# SmartBuoyLoRa.net
KiCad netlist of a schematic drawn in Altium Designer
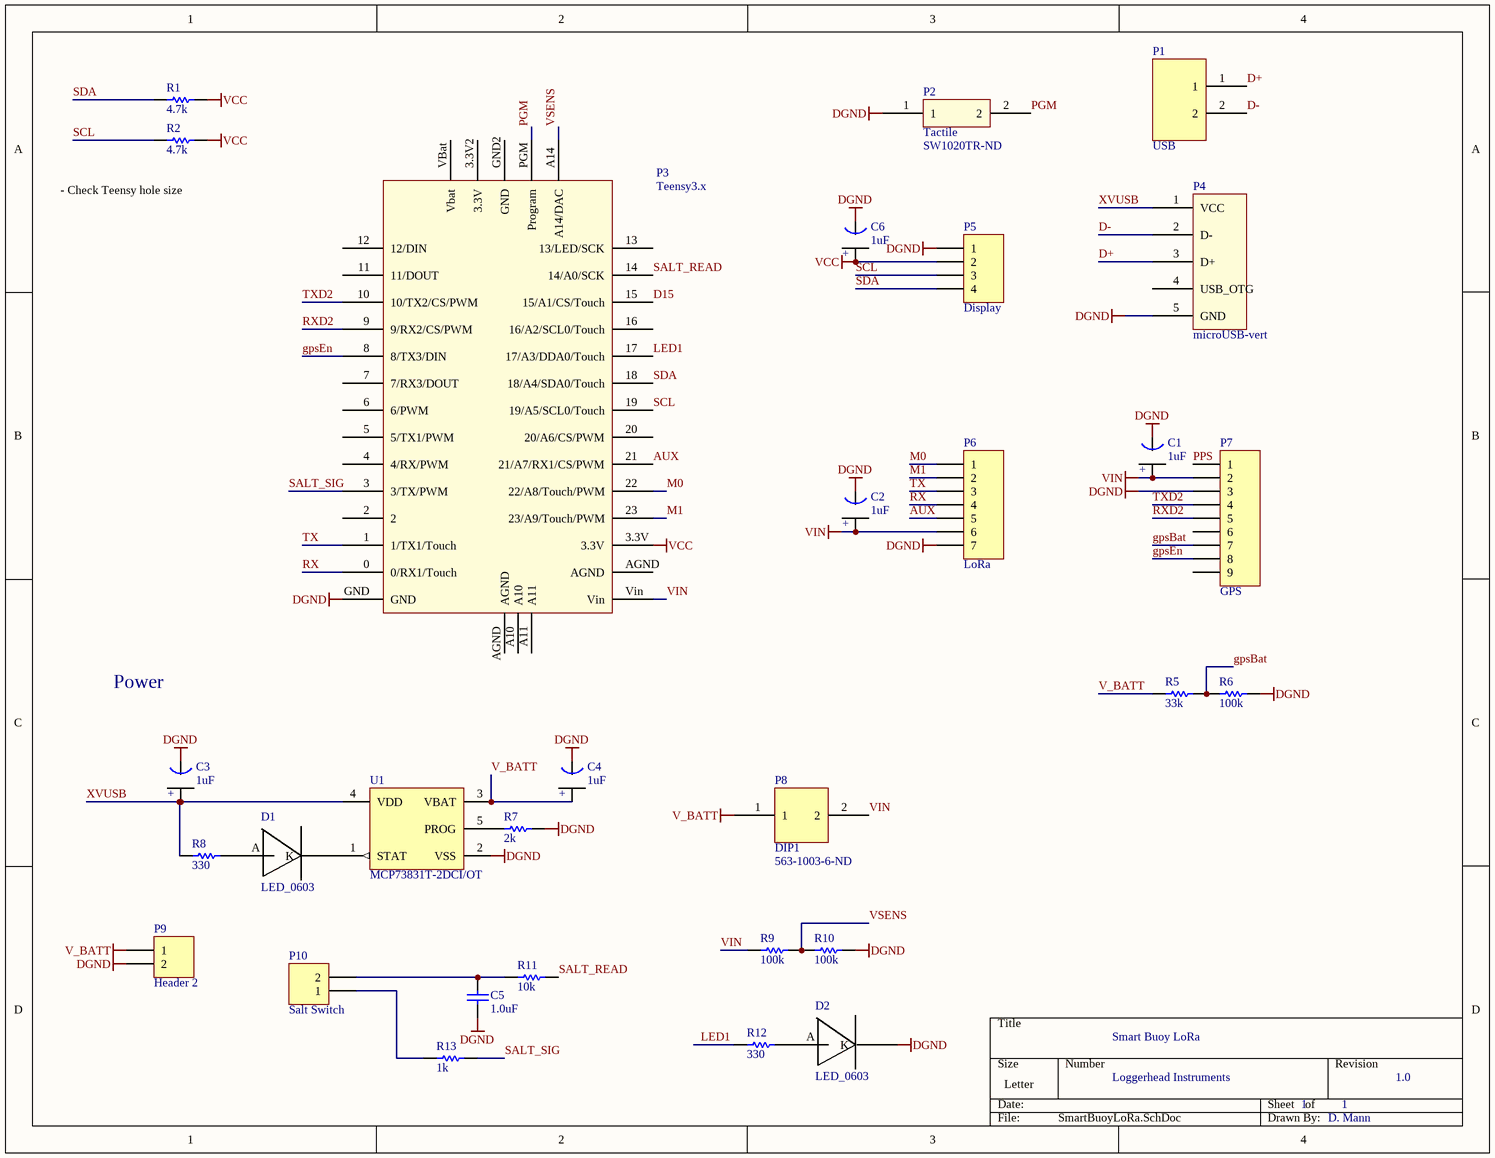
[diagram p0: SmartBuoyLoRa.SchDoc]

(export (version "E")
  (design (tool "Eeschema 10.0.6"))
  (components
    (comp (ref "C1") (value "1uF") (footprint "Tant0805") (libsource (lib "Loggerhead") (part "Tant0805")))
    (comp (ref "C2") (value "1uF") (footprint "Tant0805") (libsource (lib "Loggerhead") (part "Tant0805")))
    (comp (ref "C3") (value "1uF") (footprint "Tant0805") (libsource (lib "Loggerhead") (part "Tant0805")))
    (comp (ref "C4") (value "1uF") (footprint "Tant0805") (libsource (lib "Loggerhead") (part "Tant0805")))
    (comp (ref "C5")
      (value "1.0uF")
      (footprint "0402")
      (description "Ceramic Chip Capacitor - Standard")
      (fields (field (name "PUBLISHER") "Altium Limited"))
      (libsource (lib "KEMET Chip Capacitor") (part "C0402"))
    )
    (comp (ref "C6") (value "1uF") (footprint "Tant0805") (libsource (lib "Loggerhead") (part "Tant0805")))
    (comp (ref "D1")
      (value "LED_0603")
      (footprint "Diode0603")
      (libsource (lib "Loggerhead") (part "LED_0603"))
    )
    (comp (ref "D2")
      (value "LED_0603")
      (footprint "Diode0603")
      (libsource (lib "Loggerhead") (part "LED_0603"))
    )
    (comp (ref "P1")
      (value "USB")
      (footprint "HDR_2x1_2mm")
      (description "Charging Connector")
      (libsource (lib "Loggerhead") (part "HDR_2x1_2mm"))
    )
    (comp (ref "P2")
      (value "Tactile")
      (footprint "Tactile-B3U-1000")
      (fields (field (name "SUPPLIER PART NUMBER 1") "SW1020TR-ND"))
      (libsource (lib "Loggerhead") (part "Tactile_B3U-1000"))
    )
    (comp (ref "P3")
      (value "Teensy3.x")
      (footprint "Teensy3.x")
      (libsource (lib "Teensy") (part "Teensy3.x"))
    )
    (comp (ref "P4")
      (value "microUSB-vert")
      (footprint "MICROUSB-VERT")
      (description "Molex 105133-0011")
      (libsource (lib "Loggerhead") (part "microUSB-vert"))
    )
    (comp (ref "P5")
      (value "Display")
      (footprint "HDR1X4")
      (description "Header, 4-Pin")
      (fields (field (name "PUBLISHER") "Altium Limited"))
      (libsource (lib "Miscellaneous Connectors") (part "Header 4"))
    )
    (comp (ref "P6")
      (value "LoRa")
      (footprint "HDR1X7")
      (description "Header, 7-Pin")
      (fields (field (name "PUBLISHER") "Altium Limited"))
      (libsource (lib "Miscellaneous Connectors") (part "Header 7"))
    )
    (comp (ref "P7")
      (value "GPS")
      (footprint "HDR1X9")
      (description "Header, 9-Pin")
      (fields (field (name "PUBLISHER") "Altium Limited"))
      (libsource (lib "Miscellaneous Connectors") (part "Header 9"))
    )
    (comp (ref "P8")
      (value "DIP1")
      (footprint "DIP1")
      (fields (field (name "SUPPLIER PART NUMBER 1") "563-1003-6-ND"))
      (libsource (lib "Loggerhead") (part "DIP1"))
    )
    (comp (ref "P9")
      (value "Header 2")
      (footprint "HDR1X2")
      (description "Header, 2-Pin")
      (fields (field (name "PUBLISHER") "Altium Limited"))
      (libsource (lib "") (part "Header 2_1"))
    )
    (comp (ref "P10")
      (value "Salt Switch")
      (footprint "HDR1X2")
      (description "Header, 2-Pin")
      (fields (field (name "PUBLISHER") "Altium Limited"))
      (libsource (lib "Miscellaneous Connectors") (part "Header 2"))
    )
    (comp (ref "R1")
      (value "4.7k")
      (footprint "3-0603")
      (fields (field (name "PUBLISHER") "Altium Limited"))
      (libsource (lib "Panasonic Resistor") (part "ERJ3RK"))
    )
    (comp (ref "R2")
      (value "4.7k")
      (footprint "3-0603")
      (fields (field (name "PUBLISHER") "Altium Limited"))
      (libsource (lib "Panasonic Resistor") (part "ERJ3RK"))
    )
    (comp (ref "R5")
      (value "33k")
      (footprint "3-0603")
      (fields (field (name "PUBLISHER") "Altium Limited"))
      (libsource (lib "Panasonic Resistor") (part "ERJ3RK"))
    )
    (comp (ref "R6")
      (value "100k")
      (footprint "3-0603")
      (fields (field (name "PUBLISHER") "Altium Limited"))
      (libsource (lib "Panasonic Resistor") (part "ERJ3RK"))
    )
    (comp (ref "R7")
      (value "2k")
      (footprint "3-0603")
      (fields (field (name "PUBLISHER") "Altium Limited"))
      (libsource (lib "Panasonic Resistor") (part "ERJ3RK"))
    )
    (comp (ref "R8")
      (value "330")
      (footprint "3-0603")
      (fields (field (name "PUBLISHER") "Altium Limited"))
      (libsource (lib "Panasonic Resistor") (part "ERJ3RK"))
    )
    (comp (ref "R9")
      (value "100k")
      (footprint "3-0603")
      (fields (field (name "PUBLISHER") "Altium Limited"))
      (libsource (lib "Panasonic Resistor") (part "ERJ3RK"))
    )
    (comp (ref "R10")
      (value "100k")
      (footprint "3-0603")
      (fields (field (name "PUBLISHER") "Altium Limited"))
      (libsource (lib "Panasonic Resistor") (part "ERJ3RK"))
    )
    (comp (ref "R11")
      (value "10k")
      (footprint "3-0603")
      (fields (field (name "PUBLISHER") "Altium Limited"))
      (libsource (lib "Panasonic Resistor") (part "ERJ3RK"))
    )
    (comp (ref "R12")
      (value "330")
      (footprint "3-0603")
      (fields (field (name "PUBLISHER") "Altium Limited"))
      (libsource (lib "Panasonic Resistor") (part "ERJ3RK"))
    )
    (comp (ref "R13")
      (value "1k")
      (footprint "3-0603")
      (fields (field (name "PUBLISHER") "Altium Limited"))
      (libsource (lib "Panasonic Resistor") (part "ERJ3RK"))
    )
    (comp (ref "U1")
      (value "MCP73831T-2DCI/OT")
      (footprint "SOT-23-OT5_N")
      (libsource (lib "Microchip Power Management Battery Management") (part "MCP73831T-2DCI/OT"))
    )
  )
  (nets
    (net (code "1") (name "/AUX") (class "Default")
      (node (ref "P3") (pin "21") (pinfunction "21/A7/RX1/CS/PWM_21") (pintype "passive"))
      (node (ref "P6") (pin "5") (pinfunction "5_5") (pintype "passive"))
    )
    (net (code "2") (name "/D+") (class "Default")
      (node (ref "P1") (pin "1") (pinfunction "1_1") (pintype "passive"))
      (node (ref "P4") (pin "3") (pinfunction "D+_3") (pintype "passive"))
    )
    (net (code "3") (name "/D-") (class "Default")
      (node (ref "P1") (pin "2") (pinfunction "2_2") (pintype "passive"))
      (node (ref "P4") (pin "2") (pinfunction "D-_2") (pintype "passive"))
    )
    (net (code "4") (name "/D15") (class "Default")
      (node (ref "P3") (pin "15") (pinfunction "15/A1/CS/Touch_15") (pintype "passive"))
    )
    (net (code "5") (name "/LED1") (class "Default")
      (node (ref "P3") (pin "17") (pinfunction "17/A3/DDA0/Touch_17") (pintype "passive"))
      (node (ref "R12") (pin "1") (pinfunction "1_1") (pintype "passive"))
    )
    (net (code "6") (name "/M0") (class "Default")
      (node (ref "P3") (pin "22") (pinfunction "22/A8/Touch/PWM_22") (pintype "passive"))
      (node (ref "P6") (pin "1") (pinfunction "1_1") (pintype "passive"))
    )
    (net (code "7") (name "/M1") (class "Default")
      (node (ref "P3") (pin "23") (pinfunction "23/A9/Touch/PWM_23") (pintype "passive"))
      (node (ref "P6") (pin "2") (pinfunction "2_2") (pintype "passive"))
    )
    (net (code "8") (name "/PGM") (class "Default")
      (node (ref "P2") (pin "2") (pinfunction "2_2") (pintype "passive"))
      (node (ref "P3") (pin "PGM") (pinfunction "Program_PGM") (pintype "passive"))
    )
    (net (code "9") (name "/PPS") (class "Default")
      (node (ref "P7") (pin "1") (pinfunction "1_1") (pintype "passive"))
    )
    (net (code "10") (name "/RX") (class "Default")
      (node (ref "P3") (pin "0") (pinfunction "0/RX1/Touch_0") (pintype "passive"))
      (node (ref "P6") (pin "4") (pinfunction "4_4") (pintype "passive"))
    )
    (net (code "11") (name "/RXD2") (class "Default")
      (node (ref "P3") (pin "9") (pinfunction "9/RX2/CS/PWM_9") (pintype "passive"))
      (node (ref "P7") (pin "5") (pinfunction "5_5") (pintype "passive"))
    )
    (net (code "12") (name "/SALT_READ") (class "Default")
      (node (ref "P3") (pin "14") (pinfunction "14/A0/SCK_14") (pintype "passive"))
      (node (ref "R11") (pin "1") (pinfunction "1_1") (pintype "passive"))
    )
    (net (code "13") (name "/SALT_SIG") (class "Default")
      (node (ref "P3") (pin "3") (pinfunction "3/TX/PWM_3") (pintype "passive"))
      (node (ref "R13") (pin "2") (pinfunction "2_2") (pintype "passive"))
    )
    (net (code "14") (name "/SCL") (class "Default")
      (node (ref "P3") (pin "19") (pinfunction "19/A5/SCL0/Touch_19") (pintype "passive"))
      (node (ref "P5") (pin "3") (pinfunction "3_3") (pintype "passive"))
      (node (ref "R2") (pin "1") (pinfunction "1_1") (pintype "passive"))
    )
    (net (code "15") (name "/SDA") (class "Default")
      (node (ref "P3") (pin "18") (pinfunction "18/A4/SDA0/Touch_18") (pintype "passive"))
      (node (ref "P5") (pin "4") (pinfunction "4_4") (pintype "passive"))
      (node (ref "R1") (pin "2") (pinfunction "2_2") (pintype "passive"))
    )
    (net (code "16") (name "/TX") (class "Default")
      (node (ref "P3") (pin "1") (pinfunction "1/TX1/Touch_1") (pintype "passive"))
      (node (ref "P6") (pin "3") (pinfunction "3_3") (pintype "passive"))
    )
    (net (code "17") (name "/TXD2") (class "Default")
      (node (ref "P3") (pin "10") (pinfunction "10/TX2/CS/PWM_10") (pintype "passive"))
      (node (ref "P7") (pin "4") (pinfunction "4_4") (pintype "passive"))
    )
    (net (code "18") (name "/VSENS") (class "Default")
      (node (ref "P3") (pin "A14") (pinfunction "A14/DAC_A14") (pintype "passive"))
      (node (ref "R10") (pin "2") (pinfunction "2_2") (pintype "passive"))
      (node (ref "R9") (pin "1") (pinfunction "1_1") (pintype "passive"))
    )
    (net (code "19") (name "/XVUSB") (class "Default")
      (node (ref "C3") (pin "2") (pinfunction "+_2") (pintype "passive"))
      (node (ref "P4") (pin "1") (pinfunction "VCC_1") (pintype "passive"))
      (node (ref "R8") (pin "1") (pinfunction "1_1") (pintype "passive"))
      (node (ref "U1") (pin "4") (pinfunction "VDD_4") (pintype "power_in"))
    )
    (net (code "20") (name "/gpsBat") (class "Default")
      (node (ref "P7") (pin "7") (pinfunction "7_7") (pintype "passive"))
      (node (ref "R5") (pin "1") (pinfunction "1_1") (pintype "passive"))
      (node (ref "R6") (pin "2") (pinfunction "2_2") (pintype "passive"))
    )
    (net (code "21") (name "/gpsEn") (class "Default")
      (node (ref "P3") (pin "8") (pinfunction "8/TX3/DIN_8") (pintype "passive"))
      (node (ref "P7") (pin "8") (pinfunction "8_8") (pintype "passive"))
    )
    (net (code "22") (name "DGND") (class "Default")
      (node (ref "C1") (pin "1") (pinfunction "GND_1") (pintype "passive"))
      (node (ref "C2") (pin "1") (pinfunction "GND_1") (pintype "passive"))
      (node (ref "C3") (pin "1") (pinfunction "GND_1") (pintype "passive"))
      (node (ref "C4") (pin "1") (pinfunction "GND_1") (pintype "passive"))
      (node (ref "C5") (pin "2") (pinfunction "2_2") (pintype "passive"))
      (node (ref "C6") (pin "1") (pinfunction "GND_1") (pintype "passive"))
      (node (ref "D2") (pin "K") (pinfunction "K_K") (pintype "passive"))
      (node (ref "P2") (pin "1") (pinfunction "1_1") (pintype "passive"))
      (node (ref "P3") (pin "GND") (pinfunction "GND_GND") (pintype "passive"))
      (node (ref "P4") (pin "5") (pinfunction "GND_5") (pintype "passive"))
      (node (ref "P5") (pin "1") (pinfunction "1_1") (pintype "passive"))
      (node (ref "P6") (pin "7") (pinfunction "7_7") (pintype "passive"))
      (node (ref "P7") (pin "3") (pinfunction "3_3") (pintype "passive"))
      (node (ref "P9") (pin "2") (pinfunction "2_2") (pintype "passive"))
      (node (ref "R10") (pin "1") (pinfunction "1_1") (pintype "passive"))
      (node (ref "R6") (pin "1") (pinfunction "1_1") (pintype "passive"))
      (node (ref "R7") (pin "1") (pinfunction "1_1") (pintype "passive"))
      (node (ref "U1") (pin "2") (pinfunction "VSS_2") (pintype "power_in"))
    )
    (net (code "23") (name "Net-(C5-Pad1)") (class "Default")
      (node (ref "C5") (pin "1") (pinfunction "1_1") (pintype "passive"))
      (node (ref "P10") (pin "2") (pinfunction "2_2") (pintype "passive"))
      (node (ref "R11") (pin "2") (pinfunction "2_2") (pintype "passive"))
    )
    (net (code "24") (name "Net-(D1-PadA)") (class "Default")
      (node (ref "D1") (pin "A") (pinfunction "A_A") (pintype "passive"))
      (node (ref "R8") (pin "2") (pinfunction "2_2") (pintype "passive"))
    )
    (net (code "25") (name "Net-(D2-PadA)") (class "Default")
      (node (ref "D2") (pin "A") (pinfunction "A_A") (pintype "passive"))
      (node (ref "R12") (pin "2") (pinfunction "2_2") (pintype "passive"))
    )
    (net (code "26") (name "Net-(P10-Pad1)") (class "Default")
      (node (ref "P10") (pin "1") (pinfunction "1_1") (pintype "passive"))
      (node (ref "R13") (pin "1") (pinfunction "1_1") (pintype "passive"))
    )
    (net (code "27") (name "Net-(U1-PROG)") (class "Default")
      (node (ref "R7") (pin "2") (pinfunction "2_2") (pintype "passive"))
      (node (ref "U1") (pin "5") (pinfunction "PROG_5") (pintype "passive"))
    )
    (net (code "28") (name "Net-(U1-STAT)") (class "Default")
      (node (ref "D1") (pin "K") (pinfunction "K_K") (pintype "passive"))
      (node (ref "U1") (pin "1") (pinfunction "STAT_1") (pintype "output"))
    )
    (net (code "29") (name "VCC") (class "Default")
      (node (ref "C6") (pin "2") (pinfunction "+_2") (pintype "passive"))
      (node (ref "P3") (pin "3.3V") (pinfunction "3.3V_3.3V") (pintype "passive"))
      (node (ref "P5") (pin "2") (pinfunction "2_2") (pintype "passive"))
      (node (ref "R1") (pin "1") (pinfunction "1_1") (pintype "passive"))
      (node (ref "R2") (pin "2") (pinfunction "2_2") (pintype "passive"))
    )
    (net (code "30") (name "VIN") (class "Default")
      (node (ref "C1") (pin "2") (pinfunction "+_2") (pintype "passive"))
      (node (ref "C2") (pin "2") (pinfunction "+_2") (pintype "passive"))
      (node (ref "P3") (pin "Vin") (pinfunction "Vin_Vin") (pintype "passive"))
      (node (ref "P6") (pin "6") (pinfunction "6_6") (pintype "passive"))
      (node (ref "P7") (pin "2") (pinfunction "2_2") (pintype "passive"))
      (node (ref "P8") (pin "2") (pinfunction "2_2") (pintype "passive"))
      (node (ref "R9") (pin "2") (pinfunction "2_2") (pintype "passive"))
    )
    (net (code "31") (name "V_BATT") (class "Default")
      (node (ref "C4") (pin "2") (pinfunction "+_2") (pintype "passive"))
      (node (ref "P8") (pin "1") (pinfunction "1_1") (pintype "passive"))
      (node (ref "P9") (pin "1") (pinfunction "1_1") (pintype "passive"))
      (node (ref "R5") (pin "2") (pinfunction "2_2") (pintype "passive"))
      (node (ref "U1") (pin "3") (pinfunction "VBAT_3") (pintype "power_in"))
    )
    (net (code "32") (name "unconnected-(P3-3.3V-Pad3.3V2)") (class "Default")
      (node (ref "P3") (pin "3.3V2") (pinfunction "3.3V_3.3V2") (pintype "passive"))
    )
    (net (code "33") (name "unconnected-(P3-4{slash}RX{slash}PWM-Pad4)") (class "Default")
      (node (ref "P3") (pin "4") (pinfunction "4/RX/PWM_4") (pintype "passive"))
    )
    (net (code "34") (name "unconnected-(P3-5{slash}TX1{slash}PWM-Pad5)") (class "Default")
      (node (ref "P3") (pin "5") (pinfunction "5/TX1/PWM_5") (pintype "passive"))
    )
    (net (code "35") (name "unconnected-(P3-6{slash}PWM-Pad6)") (class "Default")
      (node (ref "P3") (pin "6") (pinfunction "6/PWM_6") (pintype "passive"))
    )
    (net (code "36") (name "unconnected-(P3-7{slash}RX3{slash}DOUT-Pad7)") (class "Default")
      (node (ref "P3") (pin "7") (pinfunction "7/RX3/DOUT_7") (pintype "passive"))
    )
    (net (code "37") (name "unconnected-(P3-11{slash}DOUT-Pad11)") (class "Default")
      (node (ref "P3") (pin "11") (pinfunction "11/DOUT_11") (pintype "passive"))
    )
    (net (code "38") (name "unconnected-(P3-12{slash}DIN-Pad12)") (class "Default")
      (node (ref "P3") (pin "12") (pinfunction "12/DIN_12") (pintype "passive"))
    )
    (net (code "39") (name "unconnected-(P3-13{slash}LED{slash}SCK-Pad13)") (class "Default")
      (node (ref "P3") (pin "13") (pinfunction "13/LED/SCK_13") (pintype "passive"))
    )
    (net (code "40") (name "unconnected-(P3-16{slash}A2{slash}SCL0{slash}Touch-Pad16)") (class "Default")
      (node (ref "P3") (pin "16") (pinfunction "16/A2/SCL0/Touch_16") (pintype "passive"))
    )
    (net (code "41") (name "unconnected-(P3-20{slash}A6{slash}CS{slash}PWM-Pad20)") (class "Default")
      (node (ref "P3") (pin "20") (pinfunction "20/A6/CS/PWM_20") (pintype "passive"))
    )
    (net (code "42") (name "unconnected-(P3-GND-PadGND2)") (class "Default")
      (node (ref "P3") (pin "GND2") (pinfunction "GND_GND2") (pintype "passive"))
    )
    (net (code "43") (name "unconnected-(P3-Pad2)") (class "Default")
      (node (ref "P3") (pin "2") (pinfunction "2_2") (pintype "passive"))
    )
    (net (code "44") (name "unconnected-(P3-PadA10)") (class "Default")
      (node (ref "P3") (pin "A10") (pinfunction "A10_A10") (pintype "passive"))
    )
    (net (code "45") (name "unconnected-(P3-PadA11)") (class "Default")
      (node (ref "P3") (pin "A11") (pinfunction "A11_A11") (pintype "passive"))
    )
    (net (code "46") (name "unconnected-(P3-PadAGND)") (class "Default")
      (node (ref "P3") (pin "AGND") (pinfunction "AGND_AGND") (pintype "passive"))
    )
    (net (code "47") (name "unconnected-(P3-PadAGND)_1") (class "Default")
      (node (ref "P3") (pin "AGND") (pinfunction "AGND_AGND") (pintype "passive"))
    )
    (net (code "48") (name "unconnected-(P3-Vbat-PadVBat)") (class "Default")
      (node (ref "P3") (pin "VBat") (pinfunction "Vbat_VBat") (pintype "passive"))
    )
    (net (code "49") (name "unconnected-(P4-USB_OTG-Pad4)") (class "Default")
      (node (ref "P4") (pin "4") (pinfunction "USB_OTG_4") (pintype "passive"))
    )
    (net (code "50") (name "unconnected-(P7-Pad6)") (class "Default")
      (node (ref "P7") (pin "6") (pinfunction "6_6") (pintype "passive"))
    )
    (net (code "51") (name "unconnected-(P7-Pad9)") (class "Default")
      (node (ref "P7") (pin "9") (pinfunction "9_9") (pintype "passive"))
    )
  )
)
